# untitled.net
KiCad netlist of a schematic drawn in EAGLE
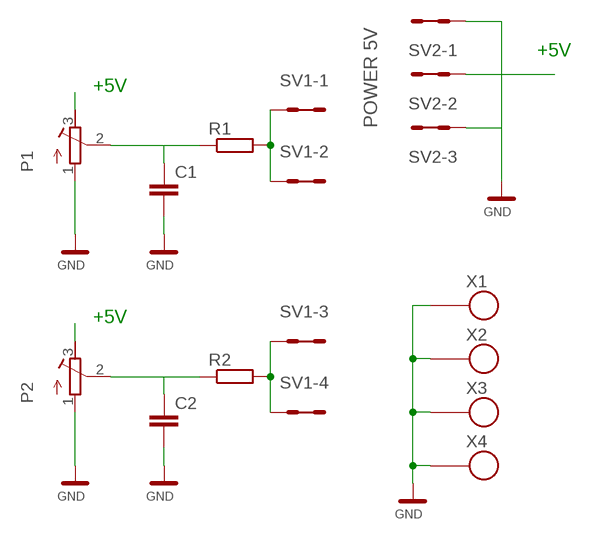
[diagram p0: schematic, sheet 1]

(export (version "E")
  (design (tool "Eeschema 10.0.6"))
  (components
    (comp (ref "C1")
      (value "C0805")
      (footprint "eagle-import:C0805")
      (libsource (lib "eagle-import") (part "C0805"))
    )
    (comp (ref "C2")
      (value "C0805")
      (footprint "eagle-import:C0805")
      (libsource (lib "eagle-import") (part "C0805"))
    )
    (comp (ref "P1")
      (value "TRIM_CA9MTV10")
      (footprint "eagle-import:TRIM_CA9MTV10")
      (libsource (lib "eagle-import") (part "TRIM_CA9MTV10"))
    )
    (comp (ref "P2")
      (value "TRIM_CA9MTV10")
      (footprint "eagle-import:TRIM_CA9MTV10")
      (libsource (lib "eagle-import") (part "TRIM_CA9MTV10"))
    )
    (comp (ref "R1")
      (value "R0805")
      (footprint "eagle-import:0805")
      (libsource (lib "eagle-import") (part "R0805"))
    )
    (comp (ref "R2")
      (value "R0805")
      (footprint "eagle-import:0805")
      (libsource (lib "eagle-import") (part "R0805"))
    )
    (comp (ref "SV1")
      (value "MA04-2")
      (footprint "eagle-import:MA04-2")
      (libsource (lib "eagle-import") (part "MA04-2"))
    )
    (comp (ref "SV2")
      (value "MA03-2")
      (footprint "eagle-import:MA03-2")
      (libsource (lib "eagle-import") (part "MA03-2"))
    )
    (comp (ref "X1")
      (value "SROUB3M")
      (footprint "eagle-import:SROUB3M")
      (libsource (lib "eagle-import") (part "SROUB3M"))
    )
    (comp (ref "X2")
      (value "SROUB3M")
      (footprint "eagle-import:SROUB3M")
      (libsource (lib "eagle-import") (part "SROUB3M"))
    )
    (comp (ref "X3")
      (value "SROUB3M")
      (footprint "eagle-import:SROUB3M")
      (libsource (lib "eagle-import") (part "SROUB3M"))
    )
    (comp (ref "X4")
      (value "SROUB3M")
      (footprint "eagle-import:SROUB3M")
      (libsource (lib "eagle-import") (part "SROUB3M"))
    )
  )
  (nets
    (net (code "1") (name "/+5V") (class "Default")
      (node (ref "P1") (pin "3") (pinfunction "3_3") (pintype "passive"))
      (node (ref "P2") (pin "3") (pinfunction "3_3") (pintype "passive"))
      (node (ref "SV2") (pin "3") (pinfunction "K_3") (pintype "passive"))
      (node (ref "SV2") (pin "4") (pinfunction "K_4") (pintype "passive"))
    )
    (net (code "2") (name "GND") (class "Default")
      (node (ref "C1") (pin "2") (pinfunction "2_2") (pintype "passive"))
      (node (ref "C2") (pin "2") (pinfunction "2_2") (pintype "passive"))
      (node (ref "P1") (pin "1") (pinfunction "1_1") (pintype "passive"))
      (node (ref "P2") (pin "1") (pinfunction "1_1") (pintype "passive"))
      (node (ref "SV2") (pin "1") (pinfunction "K_1") (pintype "passive"))
      (node (ref "SV2") (pin "2") (pinfunction "K_2") (pintype "passive"))
      (node (ref "SV2") (pin "5") (pinfunction "K_5") (pintype "passive"))
      (node (ref "SV2") (pin "6") (pinfunction "K_6") (pintype "passive"))
      (node (ref "X1") (pin "P$1") (pinfunction "P$1_P$1") (pintype "bidirectional"))
      (node (ref "X2") (pin "P$1") (pinfunction "P$1_P$1") (pintype "bidirectional"))
      (node (ref "X3") (pin "P$1") (pinfunction "P$1_P$1") (pintype "bidirectional"))
      (node (ref "X4") (pin "P$1") (pinfunction "P$1_P$1") (pintype "bidirectional"))
    )
    (net (code "3") (name "Net-(C1-Pad1)") (class "Default")
      (node (ref "C1") (pin "1") (pinfunction "1_1") (pintype "passive"))
      (node (ref "P1") (pin "2") (pinfunction "2_2") (pintype "passive"))
      (node (ref "R1") (pin "1") (pinfunction "1_1") (pintype "passive"))
    )
    (net (code "4") (name "Net-(C2-Pad1)") (class "Default")
      (node (ref "C2") (pin "1") (pinfunction "1_1") (pintype "passive"))
      (node (ref "P2") (pin "2") (pinfunction "2_2") (pintype "passive"))
      (node (ref "R2") (pin "1") (pinfunction "1_1") (pintype "passive"))
    )
    (net (code "5") (name "Net-(R1-Pad2)") (class "Default")
      (node (ref "R1") (pin "2") (pinfunction "2_2") (pintype "passive"))
      (node (ref "SV1") (pin "1") (pinfunction "K_1") (pintype "passive"))
      (node (ref "SV1") (pin "2") (pinfunction "K_2") (pintype "passive"))
      (node (ref "SV1") (pin "3") (pinfunction "K_3") (pintype "passive"))
      (node (ref "SV1") (pin "4") (pinfunction "K_4") (pintype "passive"))
    )
    (net (code "6") (name "Net-(R2-Pad2)") (class "Default")
      (node (ref "R2") (pin "2") (pinfunction "2_2") (pintype "passive"))
      (node (ref "SV1") (pin "5") (pinfunction "K_5") (pintype "passive"))
      (node (ref "SV1") (pin "6") (pinfunction "K_6") (pintype "passive"))
      (node (ref "SV1") (pin "7") (pinfunction "K_7") (pintype "passive"))
      (node (ref "SV1") (pin "8") (pinfunction "K_8") (pintype "passive"))
    )
  )
)
